# PiezoAmpBoard.net
KiCad netlist of a schematic drawn in EAGLE
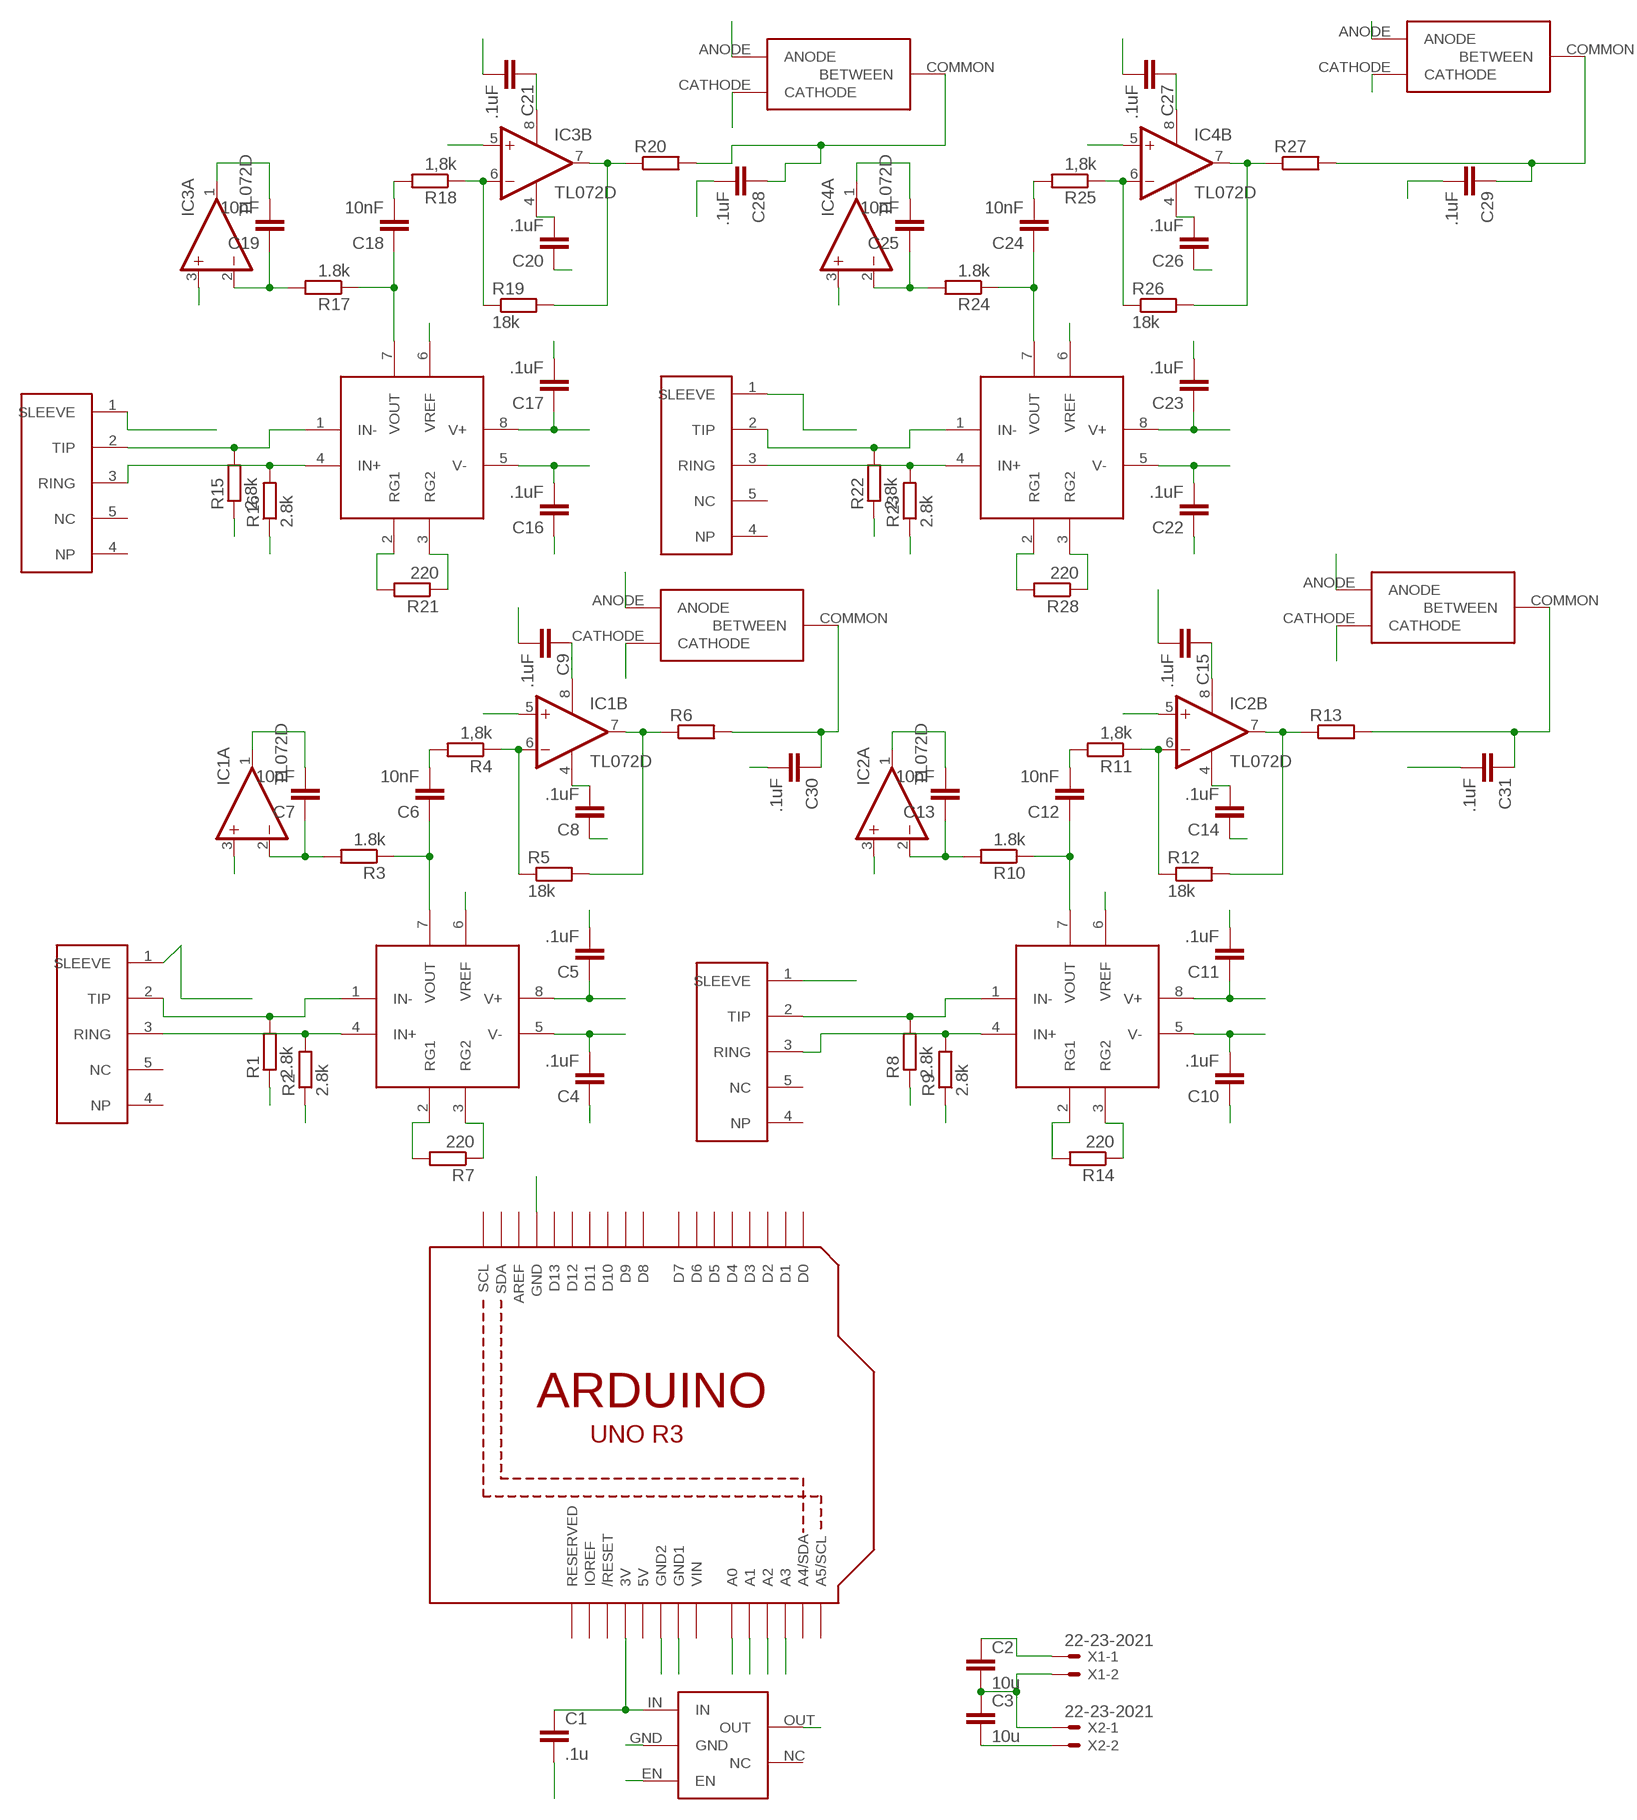
[diagram p0: schematic, sheet 1]

(export (version "E")
  (design (tool "Eeschema 10.0.6"))
  (components
    (comp (ref "C1")
      (value ".1u")
      (footprint "eagle-import:C0603")
      (libsource (lib "eagle-import") (part "C-EUC0603"))
    )
    (comp (ref "C2")
      (value "10u")
      (footprint "eagle-import:C0603")
      (libsource (lib "eagle-import") (part "C-EUC0603"))
    )
    (comp (ref "C3")
      (value "10u")
      (footprint "eagle-import:C0603")
      (libsource (lib "eagle-import") (part "C-EUC0603"))
    )
    (comp (ref "C4")
      (value ".1uF")
      (footprint "eagle-import:C0603")
      (libsource (lib "eagle-import") (part "CC0603"))
    )
    (comp (ref "C5")
      (value ".1uF")
      (footprint "eagle-import:C0603")
      (libsource (lib "eagle-import") (part "CC0603"))
    )
    (comp (ref "C6")
      (value "10nF")
      (footprint "eagle-import:C0603")
      (libsource (lib "eagle-import") (part "CC0603"))
    )
    (comp (ref "C7")
      (value "10nF")
      (footprint "eagle-import:C0603")
      (libsource (lib "eagle-import") (part "CC0603"))
    )
    (comp (ref "C8")
      (value ".1uF")
      (footprint "eagle-import:C0603")
      (libsource (lib "eagle-import") (part "CC0603"))
    )
    (comp (ref "C9")
      (value ".1uF")
      (footprint "eagle-import:C0603")
      (libsource (lib "eagle-import") (part "CC0603"))
    )
    (comp (ref "C10")
      (value ".1uF")
      (footprint "eagle-import:C0603")
      (libsource (lib "eagle-import") (part "CC0603"))
    )
    (comp (ref "C11")
      (value ".1uF")
      (footprint "eagle-import:C0603")
      (libsource (lib "eagle-import") (part "CC0603"))
    )
    (comp (ref "C12")
      (value "10nF")
      (footprint "eagle-import:C0603")
      (libsource (lib "eagle-import") (part "CC0603"))
    )
    (comp (ref "C13")
      (value "10nF")
      (footprint "eagle-import:C0603")
      (libsource (lib "eagle-import") (part "CC0603"))
    )
    (comp (ref "C14")
      (value ".1uF")
      (footprint "eagle-import:C0603")
      (libsource (lib "eagle-import") (part "CC0603"))
    )
    (comp (ref "C15")
      (value ".1uF")
      (footprint "eagle-import:C0603")
      (libsource (lib "eagle-import") (part "CC0603"))
    )
    (comp (ref "C16")
      (value ".1uF")
      (footprint "eagle-import:C0603")
      (libsource (lib "eagle-import") (part "CC0603"))
    )
    (comp (ref "C17")
      (value ".1uF")
      (footprint "eagle-import:C0603")
      (libsource (lib "eagle-import") (part "CC0603"))
    )
    (comp (ref "C18")
      (value "10nF")
      (footprint "eagle-import:C0603")
      (libsource (lib "eagle-import") (part "CC0603"))
    )
    (comp (ref "C19")
      (value "10nF")
      (footprint "eagle-import:C0603")
      (libsource (lib "eagle-import") (part "CC0603"))
    )
    (comp (ref "C20")
      (value ".1uF")
      (footprint "eagle-import:C0603")
      (libsource (lib "eagle-import") (part "CC0603"))
    )
    (comp (ref "C21")
      (value ".1uF")
      (footprint "eagle-import:C0603")
      (libsource (lib "eagle-import") (part "CC0603"))
    )
    (comp (ref "C22")
      (value ".1uF")
      (footprint "eagle-import:C0603")
      (libsource (lib "eagle-import") (part "CC0603"))
    )
    (comp (ref "C23")
      (value ".1uF")
      (footprint "eagle-import:C0603")
      (libsource (lib "eagle-import") (part "CC0603"))
    )
    (comp (ref "C24")
      (value "10nF")
      (footprint "eagle-import:C0603")
      (libsource (lib "eagle-import") (part "CC0603"))
    )
    (comp (ref "C25")
      (value "10nF")
      (footprint "eagle-import:C0603")
      (libsource (lib "eagle-import") (part "CC0603"))
    )
    (comp (ref "C26")
      (value ".1uF")
      (footprint "eagle-import:C0603")
      (libsource (lib "eagle-import") (part "CC0603"))
    )
    (comp (ref "C27")
      (value ".1uF")
      (footprint "eagle-import:C0603")
      (libsource (lib "eagle-import") (part "CC0603"))
    )
    (comp (ref "C28")
      (value ".1uF")
      (footprint "eagle-import:C0603")
      (libsource (lib "eagle-import") (part "CC0603"))
    )
    (comp (ref "C29")
      (value ".1uF")
      (footprint "eagle-import:C0603")
      (libsource (lib "eagle-import") (part "CC0603"))
    )
    (comp (ref "C30")
      (value ".1uF")
      (footprint "eagle-import:C0603")
      (libsource (lib "eagle-import") (part "CC0603"))
    )
    (comp (ref "C31")
      (value ".1uF")
      (footprint "eagle-import:C0603")
      (libsource (lib "eagle-import") (part "CC0603"))
    )
    (comp (ref "IC1")
      (value "TL072D")
      (footprint "eagle-import:SO08")
      (libsource (lib "eagle-import") (part "TL072D"))
    )
    (comp (ref "IC2")
      (value "TL072D")
      (footprint "eagle-import:SO08")
      (libsource (lib "eagle-import") (part "TL072D"))
    )
    (comp (ref "IC3")
      (value "TL072D")
      (footprint "eagle-import:SO08")
      (libsource (lib "eagle-import") (part "TL072D"))
    )
    (comp (ref "IC4")
      (value "TL072D")
      (footprint "eagle-import:SO08")
      (libsource (lib "eagle-import") (part "TL072D"))
    )
    (comp (ref "R1")
      (value "2.8k")
      (footprint "eagle-import:R0603")
      (libsource (lib "eagle-import") (part "R-EU_R0603"))
    )
    (comp (ref "R2")
      (value "2.8k")
      (footprint "eagle-import:R0603")
      (libsource (lib "eagle-import") (part "R-EU_R0603"))
    )
    (comp (ref "R3")
      (value "1.8k")
      (footprint "eagle-import:R0603")
      (libsource (lib "eagle-import") (part "R-EU_R0603"))
    )
    (comp (ref "R4")
      (value "1,8k")
      (footprint "eagle-import:R0603")
      (libsource (lib "eagle-import") (part "R-EU_R0603"))
    )
    (comp (ref "R5")
      (value "18k")
      (footprint "eagle-import:R0603")
      (libsource (lib "eagle-import") (part "R-EU_R0603"))
    )
    (comp (ref "R6")
      (value "R-EU_R0603")
      (footprint "eagle-import:R0603")
      (libsource (lib "eagle-import") (part "R-EU_R0603"))
    )
    (comp (ref "R7")
      (value "220")
      (footprint "eagle-import:R0603")
      (libsource (lib "eagle-import") (part "R-EU_R0603"))
    )
    (comp (ref "R8")
      (value "2.8k")
      (footprint "eagle-import:R0603")
      (libsource (lib "eagle-import") (part "R-EU_R0603"))
    )
    (comp (ref "R9")
      (value "2.8k")
      (footprint "eagle-import:R0603")
      (libsource (lib "eagle-import") (part "R-EU_R0603"))
    )
    (comp (ref "R10")
      (value "1.8k")
      (footprint "eagle-import:R0603")
      (libsource (lib "eagle-import") (part "R-EU_R0603"))
    )
    (comp (ref "R11")
      (value "1,8k")
      (footprint "eagle-import:R0603")
      (libsource (lib "eagle-import") (part "R-EU_R0603"))
    )
    (comp (ref "R12")
      (value "18k")
      (footprint "eagle-import:R0603")
      (libsource (lib "eagle-import") (part "R-EU_R0603"))
    )
    (comp (ref "R13")
      (value "R-EU_R0603")
      (footprint "eagle-import:R0603")
      (libsource (lib "eagle-import") (part "R-EU_R0603"))
    )
    (comp (ref "R14")
      (value "220")
      (footprint "eagle-import:R0603")
      (libsource (lib "eagle-import") (part "R-EU_R0603"))
    )
    (comp (ref "R15")
      (value "2.8k")
      (footprint "eagle-import:R0603")
      (libsource (lib "eagle-import") (part "R-EU_R0603"))
    )
    (comp (ref "R16")
      (value "2.8k")
      (footprint "eagle-import:R0603")
      (libsource (lib "eagle-import") (part "R-EU_R0603"))
    )
    (comp (ref "R17")
      (value "1.8k")
      (footprint "eagle-import:R0603")
      (libsource (lib "eagle-import") (part "R-EU_R0603"))
    )
    (comp (ref "R18")
      (value "1,8k")
      (footprint "eagle-import:R0603")
      (libsource (lib "eagle-import") (part "R-EU_R0603"))
    )
    (comp (ref "R19")
      (value "18k")
      (footprint "eagle-import:R0603")
      (libsource (lib "eagle-import") (part "R-EU_R0603"))
    )
    (comp (ref "R20")
      (value "R-EU_R0603")
      (footprint "eagle-import:R0603")
      (libsource (lib "eagle-import") (part "R-EU_R0603"))
    )
    (comp (ref "R21")
      (value "220")
      (footprint "eagle-import:R0603")
      (libsource (lib "eagle-import") (part "R-EU_R0603"))
    )
    (comp (ref "R22")
      (value "2.8k")
      (footprint "eagle-import:R0603")
      (libsource (lib "eagle-import") (part "R-EU_R0603"))
    )
    (comp (ref "R23")
      (value "2.8k")
      (footprint "eagle-import:R0603")
      (libsource (lib "eagle-import") (part "R-EU_R0603"))
    )
    (comp (ref "R24")
      (value "1.8k")
      (footprint "eagle-import:R0603")
      (libsource (lib "eagle-import") (part "R-EU_R0603"))
    )
    (comp (ref "R25")
      (value "1,8k")
      (footprint "eagle-import:R0603")
      (libsource (lib "eagle-import") (part "R-EU_R0603"))
    )
    (comp (ref "R26")
      (value "18k")
      (footprint "eagle-import:R0603")
      (libsource (lib "eagle-import") (part "R-EU_R0603"))
    )
    (comp (ref "R27")
      (value "R-EU_R0603")
      (footprint "eagle-import:R0603")
      (libsource (lib "eagle-import") (part "R-EU_R0603"))
    )
    (comp (ref "R28")
      (value "220")
      (footprint "eagle-import:R0603")
      (libsource (lib "eagle-import") (part "R-EU_R0603"))
    )
    (comp (ref "U$1")
      (value "TPS76316")
      (footprint "eagle-import:PDSO")
      (libsource (lib "eagle-import") (part "TPS76316"))
    )
    (comp (ref "U$2")
      (value "AD82216")
      (footprint "eagle-import:SOIC08")
      (libsource (lib "eagle-import") (part "AD82216"))
    )
    (comp (ref "U$3")
      (value "AD82216")
      (footprint "eagle-import:SOIC08")
      (libsource (lib "eagle-import") (part "AD82216"))
    )
    (comp (ref "U$4")
      (value "AD82216")
      (footprint "eagle-import:SOIC08")
      (libsource (lib "eagle-import") (part "AD82216"))
    )
    (comp (ref "U$5")
      (value "AD82216")
      (footprint "eagle-import:SOIC08")
      (libsource (lib "eagle-import") (part "AD82216"))
    )
    (comp (ref "U$6")
      (value "BAV99T")
      (footprint "eagle-import:SOT-523")
      (libsource (lib "eagle-import") (part "BAV99T"))
    )
    (comp (ref "U$7")
      (value "BAV99T")
      (footprint "eagle-import:SOT-523")
      (libsource (lib "eagle-import") (part "BAV99T"))
    )
    (comp (ref "U$8")
      (value "BAV99T")
      (footprint "eagle-import:SOT-523")
      (libsource (lib "eagle-import") (part "BAV99T"))
    )
    (comp (ref "U$9")
      (value "BAV99T")
      (footprint "eagle-import:SOT-523")
      (libsource (lib "eagle-import") (part "BAV99T"))
    )
    (comp (ref "U$10")
      (value "3MMJACK")
      (footprint "eagle-import:1X05")
      (libsource (lib "eagle-import") (part "3MMJACK"))
    )
    (comp (ref "U$11")
      (value "3MMJACK")
      (footprint "eagle-import:1X05")
      (libsource (lib "eagle-import") (part "3MMJACK"))
    )
    (comp (ref "U$12")
      (value "3MMJACK")
      (footprint "eagle-import:1X05")
      (libsource (lib "eagle-import") (part "3MMJACK"))
    )
    (comp (ref "U$13")
      (value "3MMJACK")
      (footprint "eagle-import:1X05")
      (libsource (lib "eagle-import") (part "3MMJACK"))
    )
    (comp (ref "U1")
      (value "ARDUINOR3-BPLACE")
      (footprint "eagle-import:ARDUINOR3-BPLACE")
      (libsource (lib "eagle-import") (part "ARDUINOR3-BPLACE"))
    )
    (comp (ref "X1")
      (value "22-23-2021")
      (footprint "eagle-import:22-23-2021")
      (fields (field (name "MF") "MOLEX"))
      (libsource (lib "eagle-import") (part "22-23-2021"))
    )
    (comp (ref "X2")
      (value "22-23-2021")
      (footprint "eagle-import:22-23-2021")
      (fields (field (name "MF") "MOLEX"))
      (libsource (lib "eagle-import") (part "22-23-2021"))
    )
  )
  (nets
    (net (code "1") (name "/3.3V") (class "Default")
      (node (ref "C1") (pin "1") (pinfunction "1_1") (pintype "passive"))
      (node (ref "U$1") (pin "EN") (pinfunction "EN_EN") (pintype "bidirectional"))
      (node (ref "U$1") (pin "IN") (pinfunction "IN_IN") (pintype "bidirectional"))
      (node (ref "U$6") (pin "CATHODE") (pinfunction "CATHODE_CATHODE") (pintype "bidirectional"))
      (node (ref "U$7") (pin "CATHODE") (pinfunction "CATHODE_CATHODE") (pintype "bidirectional"))
      (node (ref "U$8") (pin "CATHODE") (pinfunction "CATHODE_CATHODE") (pintype "bidirectional"))
      (node (ref "U$9") (pin "CATHODE") (pinfunction "CATHODE_CATHODE") (pintype "bidirectional"))
      (node (ref "U1") (pin "3V") (pinfunction "3V_3V") (pintype "power_in"))
    )
    (net (code "2") (name "/5V") (class "Default")
      (node (ref "U1") (pin "5V") (pinfunction "5V_5V") (pintype "power_in"))
    )
    (net (code "3") (name "/GND") (class "Default")
      (node (ref "C1") (pin "2") (pinfunction "2_2") (pintype "passive"))
      (node (ref "U$1") (pin "GND") (pinfunction "GND_GND") (pintype "bidirectional"))
      (node (ref "U$6") (pin "ANODE") (pinfunction "ANODE_ANODE") (pintype "bidirectional"))
      (node (ref "U$7") (pin "ANODE") (pinfunction "ANODE_ANODE") (pintype "bidirectional"))
      (node (ref "U$8") (pin "ANODE") (pinfunction "ANODE_ANODE") (pintype "bidirectional"))
      (node (ref "U$9") (pin "ANODE") (pinfunction "ANODE_ANODE") (pintype "bidirectional"))
      (node (ref "U1") (pin "GND") (pinfunction "GND_GND") (pintype "power_in"))
      (node (ref "U1") (pin "GND1") (pinfunction "GND1_GND1") (pintype "power_in"))
      (node (ref "U1") (pin "GND2") (pinfunction "GND2_GND2") (pintype "power_in"))
    )
    (net (code "4") (name "/PEIZOIN1") (class "Default")
      (node (ref "C28") (pin "1") (pinfunction "1_1") (pintype "passive"))
      (node (ref "R20") (pin "2") (pinfunction "2_2") (pintype "passive"))
      (node (ref "U$6") (pin "COMMON") (pinfunction "BETWEEN_COMMON") (pintype "bidirectional"))
      (node (ref "U1") (pin "A0") (pinfunction "A0_A0") (pintype "bidirectional"))
    )
    (net (code "5") (name "/PEIZOIN2") (class "Default")
      (node (ref "C29") (pin "1") (pinfunction "1_1") (pintype "passive"))
      (node (ref "R27") (pin "2") (pinfunction "2_2") (pintype "passive"))
      (node (ref "U$7") (pin "COMMON") (pinfunction "BETWEEN_COMMON") (pintype "bidirectional"))
      (node (ref "U1") (pin "A1") (pinfunction "A1_A1") (pintype "bidirectional"))
    )
    (net (code "6") (name "/PEIZOIN3") (class "Default")
      (node (ref "C31") (pin "1") (pinfunction "1_1") (pintype "passive"))
      (node (ref "R13") (pin "2") (pinfunction "2_2") (pintype "passive"))
      (node (ref "U$9") (pin "COMMON") (pinfunction "BETWEEN_COMMON") (pintype "bidirectional"))
      (node (ref "U1") (pin "A2") (pinfunction "A2_A2") (pintype "bidirectional"))
    )
    (net (code "7") (name "/PEIZOIN4") (class "Default")
      (node (ref "C30") (pin "1") (pinfunction "1_1") (pintype "passive"))
      (node (ref "R6") (pin "2") (pinfunction "2_2") (pintype "passive"))
      (node (ref "U$8") (pin "COMMON") (pinfunction "BETWEEN_COMMON") (pintype "bidirectional"))
      (node (ref "U1") (pin "A3") (pinfunction "A3_A3") (pintype "bidirectional"))
    )
    (net (code "8") (name "/VGND") (class "Default")
      (node (ref "C10") (pin "1") (pinfunction "1_1") (pintype "passive"))
      (node (ref "C11") (pin "2") (pinfunction "2_2") (pintype "passive"))
      (node (ref "C14") (pin "1") (pinfunction "1_1") (pintype "passive"))
      (node (ref "C15") (pin "2") (pinfunction "2_2") (pintype "passive"))
      (node (ref "C16") (pin "1") (pinfunction "1_1") (pintype "passive"))
      (node (ref "C17") (pin "2") (pinfunction "2_2") (pintype "passive"))
      (node (ref "C2") (pin "2") (pinfunction "2_2") (pintype "passive"))
      (node (ref "C20") (pin "1") (pinfunction "1_1") (pintype "passive"))
      (node (ref "C21") (pin "2") (pinfunction "2_2") (pintype "passive"))
      (node (ref "C22") (pin "1") (pinfunction "1_1") (pintype "passive"))
      (node (ref "C23") (pin "2") (pinfunction "2_2") (pintype "passive"))
      (node (ref "C26") (pin "1") (pinfunction "1_1") (pintype "passive"))
      (node (ref "C27") (pin "2") (pinfunction "2_2") (pintype "passive"))
      (node (ref "C28") (pin "2") (pinfunction "2_2") (pintype "passive"))
      (node (ref "C29") (pin "2") (pinfunction "2_2") (pintype "passive"))
      (node (ref "C3") (pin "1") (pinfunction "1_1") (pintype "passive"))
      (node (ref "C30") (pin "2") (pinfunction "2_2") (pintype "passive"))
      (node (ref "C31") (pin "2") (pinfunction "2_2") (pintype "passive"))
      (node (ref "C4") (pin "1") (pinfunction "1_1") (pintype "passive"))
      (node (ref "C5") (pin "2") (pinfunction "2_2") (pintype "passive"))
      (node (ref "C8") (pin "1") (pinfunction "1_1") (pintype "passive"))
      (node (ref "C9") (pin "2") (pinfunction "2_2") (pintype "passive"))
      (node (ref "IC1") (pin "3") (pinfunction "+IN_3") (pintype "input"))
      (node (ref "IC1") (pin "5") (pinfunction "+IN_5") (pintype "input"))
      (node (ref "IC2") (pin "3") (pinfunction "+IN_3") (pintype "input"))
      (node (ref "IC2") (pin "5") (pinfunction "+IN_5") (pintype "input"))
      (node (ref "IC3") (pin "3") (pinfunction "+IN_3") (pintype "input"))
      (node (ref "IC3") (pin "5") (pinfunction "+IN_5") (pintype "input"))
      (node (ref "IC4") (pin "3") (pinfunction "+IN_3") (pintype "input"))
      (node (ref "IC4") (pin "5") (pinfunction "+IN_5") (pintype "input"))
      (node (ref "R1") (pin "1") (pinfunction "1_1") (pintype "passive"))
      (node (ref "R15") (pin "1") (pinfunction "1_1") (pintype "passive"))
      (node (ref "R16") (pin "1") (pinfunction "1_1") (pintype "passive"))
      (node (ref "R2") (pin "1") (pinfunction "1_1") (pintype "passive"))
      (node (ref "R22") (pin "1") (pinfunction "1_1") (pintype "passive"))
      (node (ref "R23") (pin "1") (pinfunction "1_1") (pintype "passive"))
      (node (ref "R8") (pin "1") (pinfunction "1_1") (pintype "passive"))
      (node (ref "R9") (pin "1") (pinfunction "1_1") (pintype "passive"))
      (node (ref "U$1") (pin "OUT") (pinfunction "OUT_OUT") (pintype "bidirectional"))
      (node (ref "U$10") (pin "1") (pinfunction "SLEEVE_1") (pintype "bidirectional"))
      (node (ref "U$11") (pin "1") (pinfunction "SLEEVE_1") (pintype "bidirectional"))
      (node (ref "U$12") (pin "1") (pinfunction "SLEEVE_1") (pintype "bidirectional"))
      (node (ref "U$13") (pin "1") (pinfunction "SLEEVE_1") (pintype "bidirectional"))
      (node (ref "X1") (pin "2") (pinfunction "S_2") (pintype "passive"))
      (node (ref "X2") (pin "1") (pinfunction "S_1") (pintype "passive"))
    )
    (net (code "9") (name "/VIN") (class "Default")
      (node (ref "U1") (pin "VIN") (pinfunction "VIN_VIN") (pintype "power_in"))
    )
    (net (code "10") (name "/VREF") (class "Default")
      (node (ref "C7") (pin "2") (pinfunction "2_2") (pintype "passive"))
      (node (ref "IC1") (pin "1") (pinfunction "OUT_1") (pintype "output"))
      (node (ref "U$2") (pin "6") (pinfunction "VREF_6") (pintype "bidirectional"))
    )
    (net (code "11") (name "/VREF1") (class "Default")
      (node (ref "C13") (pin "2") (pinfunction "2_2") (pintype "passive"))
      (node (ref "IC2") (pin "1") (pinfunction "OUT_1") (pintype "output"))
      (node (ref "U$3") (pin "6") (pinfunction "VREF_6") (pintype "bidirectional"))
    )
    (net (code "12") (name "/VREF2") (class "Default")
      (node (ref "C19") (pin "2") (pinfunction "2_2") (pintype "passive"))
      (node (ref "IC3") (pin "1") (pinfunction "OUT_1") (pintype "output"))
      (node (ref "U$4") (pin "6") (pinfunction "VREF_6") (pintype "bidirectional"))
    )
    (net (code "13") (name "/VREF3") (class "Default")
      (node (ref "C25") (pin "2") (pinfunction "2_2") (pintype "passive"))
      (node (ref "IC4") (pin "1") (pinfunction "OUT_1") (pintype "output"))
      (node (ref "U$5") (pin "6") (pinfunction "VREF_6") (pintype "bidirectional"))
    )
    (net (code "14") (name "/VS+") (class "Default")
      (node (ref "C11") (pin "1") (pinfunction "1_1") (pintype "passive"))
      (node (ref "C15") (pin "1") (pinfunction "1_1") (pintype "passive"))
      (node (ref "C17") (pin "1") (pinfunction "1_1") (pintype "passive"))
      (node (ref "C2") (pin "1") (pinfunction "1_1") (pintype "passive"))
      (node (ref "C21") (pin "1") (pinfunction "1_1") (pintype "passive"))
      (node (ref "C23") (pin "1") (pinfunction "1_1") (pintype "passive"))
      (node (ref "C27") (pin "1") (pinfunction "1_1") (pintype "passive"))
      (node (ref "C5") (pin "1") (pinfunction "1_1") (pintype "passive"))
      (node (ref "C9") (pin "1") (pinfunction "1_1") (pintype "passive"))
      (node (ref "IC1") (pin "8") (pinfunction "V+_8") (pintype "power_in"))
      (node (ref "IC2") (pin "8") (pinfunction "V+_8") (pintype "power_in"))
      (node (ref "IC3") (pin "8") (pinfunction "V+_8") (pintype "power_in"))
      (node (ref "IC4") (pin "8") (pinfunction "V+_8") (pintype "power_in"))
      (node (ref "U$2") (pin "8") (pinfunction "V+_8") (pintype "bidirectional"))
      (node (ref "U$3") (pin "8") (pinfunction "V+_8") (pintype "bidirectional"))
      (node (ref "U$4") (pin "8") (pinfunction "V+_8") (pintype "bidirectional"))
      (node (ref "U$5") (pin "8") (pinfunction "V+_8") (pintype "bidirectional"))
      (node (ref "X1") (pin "1") (pinfunction "S_1") (pintype "passive"))
    )
    (net (code "15") (name "/VS-") (class "Default")
      (node (ref "C10") (pin "2") (pinfunction "2_2") (pintype "passive"))
      (node (ref "C14") (pin "2") (pinfunction "2_2") (pintype "passive"))
      (node (ref "C16") (pin "2") (pinfunction "2_2") (pintype "passive"))
      (node (ref "C20") (pin "2") (pinfunction "2_2") (pintype "passive"))
      (node (ref "C22") (pin "2") (pinfunction "2_2") (pintype "passive"))
      (node (ref "C26") (pin "2") (pinfunction "2_2") (pintype "passive"))
      (node (ref "C3") (pin "2") (pinfunction "2_2") (pintype "passive"))
      (node (ref "C4") (pin "2") (pinfunction "2_2") (pintype "passive"))
      (node (ref "C8") (pin "2") (pinfunction "2_2") (pintype "passive"))
      (node (ref "IC1") (pin "4") (pinfunction "V-_4") (pintype "power_in"))
      (node (ref "IC2") (pin "4") (pinfunction "V-_4") (pintype "power_in"))
      (node (ref "IC3") (pin "4") (pinfunction "V-_4") (pintype "power_in"))
      (node (ref "IC4") (pin "4") (pinfunction "V-_4") (pintype "power_in"))
      (node (ref "U$2") (pin "5") (pinfunction "V-_5") (pintype "bidirectional"))
      (node (ref "U$3") (pin "5") (pinfunction "V-_5") (pintype "bidirectional"))
      (node (ref "U$4") (pin "5") (pinfunction "V-_5") (pintype "bidirectional"))
      (node (ref "U$5") (pin "5") (pinfunction "V-_5") (pintype "bidirectional"))
      (node (ref "X2") (pin "2") (pinfunction "S_2") (pintype "passive"))
    )
    (net (code "16") (name "Net-(C6-Pad2)") (class "Default")
      (node (ref "C6") (pin "2") (pinfunction "2_2") (pintype "passive"))
      (node (ref "R4") (pin "2") (pinfunction "2_2") (pintype "passive"))
    )
    (net (code "17") (name "Net-(C12-Pad2)") (class "Default")
      (node (ref "C12") (pin "2") (pinfunction "2_2") (pintype "passive"))
      (node (ref "R11") (pin "2") (pinfunction "2_2") (pintype "passive"))
    )
    (net (code "18") (name "Net-(C18-Pad2)") (class "Default")
      (node (ref "C18") (pin "2") (pinfunction "2_2") (pintype "passive"))
      (node (ref "R18") (pin "2") (pinfunction "2_2") (pintype "passive"))
    )
    (net (code "19") (name "Net-(C24-Pad2)") (class "Default")
      (node (ref "C24") (pin "2") (pinfunction "2_2") (pintype "passive"))
      (node (ref "R25") (pin "2") (pinfunction "2_2") (pintype "passive"))
    )
    (net (code "20") (name "Net-(IC1A--IN)") (class "Default")
      (node (ref "C7") (pin "1") (pinfunction "1_1") (pintype "passive"))
      (node (ref "IC1") (pin "2") (pinfunction "-IN_2") (pintype "input"))
      (node (ref "R3") (pin "2") (pinfunction "2_2") (pintype "passive"))
    )
    (net (code "21") (name "Net-(IC1B--IN)") (class "Default")
      (node (ref "IC1") (pin "6") (pinfunction "-IN_6") (pintype "input"))
      (node (ref "R4") (pin "1") (pinfunction "1_1") (pintype "passive"))
      (node (ref "R5") (pin "1") (pinfunction "1_1") (pintype "passive"))
    )
    (net (code "22") (name "Net-(IC1B-OUT)") (class "Default")
      (node (ref "IC1") (pin "7") (pinfunction "OUT_7") (pintype "output"))
      (node (ref "R5") (pin "2") (pinfunction "2_2") (pintype "passive"))
      (node (ref "R6") (pin "1") (pinfunction "1_1") (pintype "passive"))
    )
    (net (code "23") (name "Net-(IC2A--IN)") (class "Default")
      (node (ref "C13") (pin "1") (pinfunction "1_1") (pintype "passive"))
      (node (ref "IC2") (pin "2") (pinfunction "-IN_2") (pintype "input"))
      (node (ref "R10") (pin "2") (pinfunction "2_2") (pintype "passive"))
    )
    (net (code "24") (name "Net-(IC2B--IN)") (class "Default")
      (node (ref "IC2") (pin "6") (pinfunction "-IN_6") (pintype "input"))
      (node (ref "R11") (pin "1") (pinfunction "1_1") (pintype "passive"))
      (node (ref "R12") (pin "1") (pinfunction "1_1") (pintype "passive"))
    )
    (net (code "25") (name "Net-(IC2B-OUT)") (class "Default")
      (node (ref "IC2") (pin "7") (pinfunction "OUT_7") (pintype "output"))
      (node (ref "R12") (pin "2") (pinfunction "2_2") (pintype "passive"))
      (node (ref "R13") (pin "1") (pinfunction "1_1") (pintype "passive"))
    )
    (net (code "26") (name "Net-(IC3A--IN)") (class "Default")
      (node (ref "C19") (pin "1") (pinfunction "1_1") (pintype "passive"))
      (node (ref "IC3") (pin "2") (pinfunction "-IN_2") (pintype "input"))
      (node (ref "R17") (pin "2") (pinfunction "2_2") (pintype "passive"))
    )
    (net (code "27") (name "Net-(IC3B--IN)") (class "Default")
      (node (ref "IC3") (pin "6") (pinfunction "-IN_6") (pintype "input"))
      (node (ref "R18") (pin "1") (pinfunction "1_1") (pintype "passive"))
      (node (ref "R19") (pin "1") (pinfunction "1_1") (pintype "passive"))
    )
    (net (code "28") (name "Net-(IC3B-OUT)") (class "Default")
      (node (ref "IC3") (pin "7") (pinfunction "OUT_7") (pintype "output"))
      (node (ref "R19") (pin "2") (pinfunction "2_2") (pintype "passive"))
      (node (ref "R20") (pin "1") (pinfunction "1_1") (pintype "passive"))
    )
    (net (code "29") (name "Net-(IC4A--IN)") (class "Default")
      (node (ref "C25") (pin "1") (pinfunction "1_1") (pintype "passive"))
      (node (ref "IC4") (pin "2") (pinfunction "-IN_2") (pintype "input"))
      (node (ref "R24") (pin "2") (pinfunction "2_2") (pintype "passive"))
    )
    (net (code "30") (name "Net-(IC4B--IN)") (class "Default")
      (node (ref "IC4") (pin "6") (pinfunction "-IN_6") (pintype "input"))
      (node (ref "R25") (pin "1") (pinfunction "1_1") (pintype "passive"))
      (node (ref "R26") (pin "1") (pinfunction "1_1") (pintype "passive"))
    )
    (net (code "31") (name "Net-(IC4B-OUT)") (class "Default")
      (node (ref "IC4") (pin "7") (pinfunction "OUT_7") (pintype "output"))
      (node (ref "R26") (pin "2") (pinfunction "2_2") (pintype "passive"))
      (node (ref "R27") (pin "1") (pinfunction "1_1") (pintype "passive"))
    )
    (net (code "32") (name "Net-(U$2-RG1)") (class "Default")
      (node (ref "R7") (pin "2") (pinfunction "2_2") (pintype "passive"))
      (node (ref "U$2") (pin "2") (pinfunction "RG1_2") (pintype "bidirectional"))
    )
    (net (code "33") (name "Net-(U$2-RG2)") (class "Default")
      (node (ref "R7") (pin "1") (pinfunction "1_1") (pintype "passive"))
      (node (ref "U$2") (pin "3") (pinfunction "RG2_3") (pintype "bidirectional"))
    )
    (net (code "34") (name "Net-(U$2-VOUT)") (class "Default")
      (node (ref "C6") (pin "1") (pinfunction "1_1") (pintype "passive"))
      (node (ref "R3") (pin "1") (pinfunction "1_1") (pintype "passive"))
      (node (ref "U$2") (pin "7") (pinfunction "VOUT_7") (pintype "bidirectional"))
    )
    (net (code "35") (name "Net-(U$3-RG1)") (class "Default")
      (node (ref "R14") (pin "2") (pinfunction "2_2") (pintype "passive"))
      (node (ref "U$3") (pin "2") (pinfunction "RG1_2") (pintype "bidirectional"))
    )
    (net (code "36") (name "Net-(U$3-RG2)") (class "Default")
      (node (ref "R14") (pin "1") (pinfunction "1_1") (pintype "passive"))
      (node (ref "U$3") (pin "3") (pinfunction "RG2_3") (pintype "bidirectional"))
    )
    (net (code "37") (name "Net-(U$3-VOUT)") (class "Default")
      (node (ref "C12") (pin "1") (pinfunction "1_1") (pintype "passive"))
      (node (ref "R10") (pin "1") (pinfunction "1_1") (pintype "passive"))
      (node (ref "U$3") (pin "7") (pinfunction "VOUT_7") (pintype "bidirectional"))
    )
    (net (code "38") (name "Net-(U$4-RG1)") (class "Default")
      (node (ref "R21") (pin "2") (pinfunction "2_2") (pintype "passive"))
      (node (ref "U$4") (pin "2") (pinfunction "RG1_2") (pintype "bidirectional"))
    )
    (net (code "39") (name "Net-(U$4-RG2)") (class "Default")
      (node (ref "R21") (pin "1") (pinfunction "1_1") (pintype "passive"))
      (node (ref "U$4") (pin "3") (pinfunction "RG2_3") (pintype "bidirectional"))
    )
    (net (code "40") (name "Net-(U$4-VOUT)") (class "Default")
      (node (ref "C18") (pin "1") (pinfunction "1_1") (pintype "passive"))
      (node (ref "R17") (pin "1") (pinfunction "1_1") (pintype "passive"))
      (node (ref "U$4") (pin "7") (pinfunction "VOUT_7") (pintype "bidirectional"))
    )
    (net (code "41") (name "Net-(U$5-RG1)") (class "Default")
      (node (ref "R28") (pin "2") (pinfunction "2_2") (pintype "passive"))
      (node (ref "U$5") (pin "2") (pinfunction "RG1_2") (pintype "bidirectional"))
    )
    (net (code "42") (name "Net-(U$5-RG2)") (class "Default")
      (node (ref "R28") (pin "1") (pinfunction "1_1") (pintype "passive"))
      (node (ref "U$5") (pin "3") (pinfunction "RG2_3") (pintype "bidirectional"))
    )
    (net (code "43") (name "Net-(U$5-VOUT)") (class "Default")
      (node (ref "C24") (pin "1") (pinfunction "1_1") (pintype "passive"))
      (node (ref "R24") (pin "1") (pinfunction "1_1") (pintype "passive"))
      (node (ref "U$5") (pin "7") (pinfunction "VOUT_7") (pintype "bidirectional"))
    )
    (net (code "44") (name "Net-(U$10-RING)") (class "Default")
      (node (ref "R2") (pin "2") (pinfunction "2_2") (pintype "passive"))
      (node (ref "U$10") (pin "3") (pinfunction "RING_3") (pintype "bidirectional"))
      (node (ref "U$2") (pin "4") (pinfunction "IN+_4") (pintype "bidirectional"))
    )
    (net (code "45") (name "Net-(U$10-TIP)") (class "Default")
      (node (ref "R1") (pin "2") (pinfunction "2_2") (pintype "passive"))
      (node (ref "U$10") (pin "2") (pinfunction "TIP_2") (pintype "bidirectional"))
      (node (ref "U$2") (pin "1") (pinfunction "IN-_1") (pintype "bidirectional"))
    )
    (net (code "46") (name "Net-(U$11-RING)") (class "Default")
      (node (ref "R16") (pin "2") (pinfunction "2_2") (pintype "passive"))
      (node (ref "U$11") (pin "3") (pinfunction "RING_3") (pintype "bidirectional"))
      (node (ref "U$4") (pin "4") (pinfunction "IN+_4") (pintype "bidirectional"))
    )
    (net (code "47") (name "Net-(U$11-TIP)") (class "Default")
      (node (ref "R15") (pin "2") (pinfunction "2_2") (pintype "passive"))
      (node (ref "U$11") (pin "2") (pinfunction "TIP_2") (pintype "bidirectional"))
      (node (ref "U$4") (pin "1") (pinfunction "IN-_1") (pintype "bidirectional"))
    )
    (net (code "48") (name "Net-(U$12-RING)") (class "Default")
      (node (ref "R23") (pin "2") (pinfunction "2_2") (pintype "passive"))
      (node (ref "U$12") (pin "3") (pinfunction "RING_3") (pintype "bidirectional"))
      (node (ref "U$5") (pin "4") (pinfunction "IN+_4") (pintype "bidirectional"))
    )
    (net (code "49") (name "Net-(U$12-TIP)") (class "Default")
      (node (ref "R22") (pin "2") (pinfunction "2_2") (pintype "passive"))
      (node (ref "U$12") (pin "2") (pinfunction "TIP_2") (pintype "bidirectional"))
      (node (ref "U$5") (pin "1") (pinfunction "IN-_1") (pintype "bidirectional"))
    )
    (net (code "50") (name "Net-(U$13-RING)") (class "Default")
      (node (ref "R9") (pin "2") (pinfunction "2_2") (pintype "passive"))
      (node (ref "U$13") (pin "3") (pinfunction "RING_3") (pintype "bidirectional"))
      (node (ref "U$3") (pin "4") (pinfunction "IN+_4") (pintype "bidirectional"))
    )
    (net (code "51") (name "Net-(U$13-TIP)") (class "Default")
      (node (ref "R8") (pin "2") (pinfunction "2_2") (pintype "passive"))
      (node (ref "U$13") (pin "2") (pinfunction "TIP_2") (pintype "bidirectional"))
      (node (ref "U$3") (pin "1") (pinfunction "IN-_1") (pintype "bidirectional"))
    )
    (net (code "52") (name "unconnected-(U$1-PadNC)") (class "Default")
      (node (ref "U$1") (pin "NC") (pinfunction "NC_NC") (pintype "bidirectional"))
    )
    (net (code "53") (name "unconnected-(U$10-NC-Pad5)") (class "Default")
      (node (ref "U$10") (pin "5") (pinfunction "NC_5") (pintype "bidirectional"))
    )
    (net (code "54") (name "unconnected-(U$10-NP-Pad4)") (class "Default")
      (node (ref "U$10") (pin "4") (pinfunction "NP_4") (pintype "bidirectional"))
    )
    (net (code "55") (name "unconnected-(U$11-NC-Pad5)") (class "Default")
      (node (ref "U$11") (pin "5") (pinfunction "NC_5") (pintype "bidirectional"))
    )
    (net (code "56") (name "unconnected-(U$11-NP-Pad4)") (class "Default")
      (node (ref "U$11") (pin "4") (pinfunction "NP_4") (pintype "bidirectional"))
    )
    (net (code "57") (name "unconnected-(U$12-NC-Pad5)") (class "Default")
      (node (ref "U$12") (pin "5") (pinfunction "NC_5") (pintype "bidirectional"))
    )
    (net (code "58") (name "unconnected-(U$12-NP-Pad4)") (class "Default")
      (node (ref "U$12") (pin "4") (pinfunction "NP_4") (pintype "bidirectional"))
    )
    (net (code "59") (name "unconnected-(U$13-NC-Pad5)") (class "Default")
      (node (ref "U$13") (pin "5") (pinfunction "NC_5") (pintype "bidirectional"))
    )
    (net (code "60") (name "unconnected-(U$13-NP-Pad4)") (class "Default")
      (node (ref "U$13") (pin "4") (pinfunction "NP_4") (pintype "bidirectional"))
    )
    (net (code "61") (name "unconnected-(U1-A4{slash}SDA-PadA4)") (class "Default")
      (node (ref "U1") (pin "A4") (pinfunction "A4/SDA_A4") (pintype "bidirectional"))
    )
    (net (code "62") (name "unconnected-(U1-A5{slash}SCL-PadA5)") (class "Default")
      (node (ref "U1") (pin "A5") (pinfunction "A5/SCL_A5") (pintype "bidirectional"))
    )
    (net (code "63") (name "unconnected-(U1-PadAREF)") (class "Default")
      (node (ref "U1") (pin "AREF") (pinfunction "AREF_AREF") (pintype "bidirectional"))
    )
    (net (code "64") (name "unconnected-(U1-PadD0)") (class "Default")
      (node (ref "U1") (pin "D0") (pinfunction "D0_D0") (pintype "bidirectional"))
    )
    (net (code "65") (name "unconnected-(U1-PadD1)") (class "Default")
      (node (ref "U1") (pin "D1") (pinfunction "D1_D1") (pintype "bidirectional"))
    )
    (net (code "66") (name "unconnected-(U1-PadD2)") (class "Default")
      (node (ref "U1") (pin "D2") (pinfunction "D2_D2") (pintype "bidirectional"))
    )
    (net (code "67") (name "unconnected-(U1-PadD3)") (class "Default")
      (node (ref "U1") (pin "D3") (pinfunction "D3_D3") (pintype "bidirectional"))
    )
    (net (code "68") (name "unconnected-(U1-PadD4)") (class "Default")
      (node (ref "U1") (pin "D4") (pinfunction "D4_D4") (pintype "bidirectional"))
    )
    (net (code "69") (name "unconnected-(U1-PadD5)") (class "Default")
      (node (ref "U1") (pin "D5") (pinfunction "D5_D5") (pintype "bidirectional"))
    )
    (net (code "70") (name "unconnected-(U1-PadD6)") (class "Default")
      (node (ref "U1") (pin "D6") (pinfunction "D6_D6") (pintype "bidirectional"))
    )
    (net (code "71") (name "unconnected-(U1-PadD7)") (class "Default")
      (node (ref "U1") (pin "D7") (pinfunction "D7_D7") (pintype "bidirectional"))
    )
    (net (code "72") (name "unconnected-(U1-PadD8)") (class "Default")
      (node (ref "U1") (pin "D8") (pinfunction "D8_D8") (pintype "bidirectional"))
    )
    (net (code "73") (name "unconnected-(U1-PadD9)") (class "Default")
      (node (ref "U1") (pin "D9") (pinfunction "D9_D9") (pintype "bidirectional"))
    )
    (net (code "74") (name "unconnected-(U1-PadD10)") (class "Default")
      (node (ref "U1") (pin "D10") (pinfunction "D10_D10") (pintype "bidirectional"))
    )
    (net (code "75") (name "unconnected-(U1-PadD11)") (class "Default")
      (node (ref "U1") (pin "D11") (pinfunction "D11_D11") (pintype "bidirectional"))
    )
    (net (code "76") (name "unconnected-(U1-PadD12)") (class "Default")
      (node (ref "U1") (pin "D12") (pinfunction "D12_D12") (pintype "bidirectional"))
    )
    (net (code "77") (name "unconnected-(U1-PadD13)") (class "Default")
      (node (ref "U1") (pin "D13") (pinfunction "D13_D13") (pintype "bidirectional"))
    )
    (net (code "78") (name "unconnected-(U1-PadIOREF)") (class "Default")
      (node (ref "U1") (pin "IOREF") (pinfunction "IOREF_IOREF") (pintype "output"))
    )
    (net (code "79") (name "unconnected-(U1-PadRESERVED)") (class "Default")
      (node (ref "U1") (pin "RESERVED") (pinfunction "RESERVED_RESERVED") (pintype "no_connect"))
    )
    (net (code "80") (name "unconnected-(U1-PadSCL)") (class "Default")
      (node (ref "U1") (pin "SCL") (pinfunction "SCL_SCL") (pintype "bidirectional"))
    )
    (net (code "81") (name "unconnected-(U1-PadSDA)") (class "Default")
      (node (ref "U1") (pin "SDA") (pinfunction "SDA_SDA") (pintype "bidirectional"))
    )
    (net (code "82") (name "unconnected-(U1-{slash}RESET-PadRESET)") (class "Default")
      (node (ref "U1") (pin "RESET") (pinfunction "/RESET_RESET") (pintype "bidirectional"))
    )
  )
)
